# 6_Pulse_Sensor.net
KiCad netlist of a schematic drawn in Altium Designer
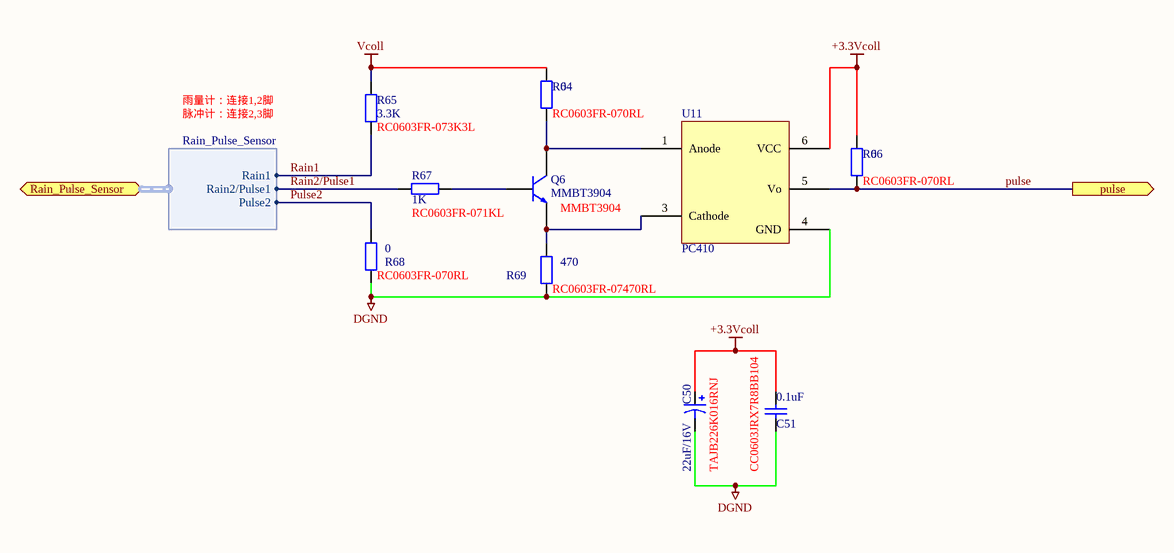
[diagram p0: 6_Pulse_Sensor.SchDoc]

(export (version "E")
  (design (tool "Eeschema 10.0.6"))
  (components
    (comp (ref "C50")
      (value "22uF/16V")
      (footprint "CB3528")
      (description "Polarized Capacitor (Radial)")
      (fields (field (name "PART NO.") "TAJB226K016RNJ"))
      (libsource (lib "Miscellaneous Devices") (part "Cap Pol1"))
    )
    (comp (ref "C51")
      (value "0.1uF")
      (footprint "CC0603")
      (description "Capacitor")
      (fields (field (name "TYPE NO.") "CC0603JRX7R8BB104"))
      (libsource (lib "Miscellaneous Devices") (part "Cap"))
    )
    (comp (ref "Q6")
      (value "MMBT3904")
      (footprint "SOT-23W")
      (fields (field (name "TYPE NO.") "MMBT3904"))
      (libsource (lib "woylib2015") (part "NPN"))
    )
    (comp (ref "R64")
      (value "0")
      (footprint "CC0603")
      (description "Resistor")
      (fields (field (name "TYPE NO.") "RC0603FR-070RL"))
      (libsource (lib "Miscellaneous Devices") (part "Res2"))
    )
    (comp (ref "R65")
      (value "3.3K")
      (footprint "CC0603")
      (description "Resistor")
      (fields (field (name "TYPE NO.") "RC0603FR-073K3L"))
      (libsource (lib "Miscellaneous Devices") (part "Res2"))
    )
    (comp (ref "R66")
      (value "0")
      (footprint "CC0603")
      (description "Resistor")
      (fields (field (name "TYPE NO.") "RC0603FR-070RL"))
      (libsource (lib "Miscellaneous Devices") (part "Res2"))
    )
    (comp (ref "R67")
      (value "1K")
      (footprint "CC0603")
      (description "Resistor")
      (fields (field (name "TYPE NO.") "RC0603FR-071KL"))
      (libsource (lib "") (part "Res2_1"))
    )
    (comp (ref "R68")
      (value "0")
      (footprint "CC0603")
      (description "Resistor")
      (fields (field (name "TYPE NO.") "RC0603FR-070RL"))
      (libsource (lib "Miscellaneous Devices") (part "Res2"))
    )
    (comp (ref "R69")
      (value "470")
      (footprint "CC0603")
      (description "Resistor")
      (fields (field (name "TYPE NO.") "RC0603FR-07470RL"))
      (libsource (lib "Miscellaneous Devices") (part "Res2"))
    )
    (comp (ref "U11") (value "PC410") (footprint "PC410") (libsource (lib "woylib2015") (part "PC410")))
  )
  (nets
    (net (code "2") (name "+3.3Vcoll") (class "Default")
      (node (ref "C50") (pin "1") (pinfunction "1_1") (pintype "passive"))
      (node (ref "C51") (pin "2") (pinfunction "2_2") (pintype "passive"))
      (node (ref "R66") (pin "1") (pinfunction "1_1") (pintype "passive"))
      (node (ref "U11") (pin "6") (pinfunction "VCC_6") (pintype "passive"))
    )
    (net (code "3") (name "/Pulse2") (class "Default")
      (node (ref "R68") (pin "1") (pinfunction "1_1") (pintype "passive"))
    )
    (net (code "4") (name "/Rain1") (class "Default")
      (node (ref "R65") (pin "2") (pinfunction "2_2") (pintype "passive"))
    )
    (net (code "5") (name "/Rain2{slash}Pulse1") (class "Default")
      (node (ref "R67") (pin "1") (pinfunction "1_1") (pintype "passive"))
    )
    (net (code "6") (name "/pulse") (class "Default")
      (node (ref "R66") (pin "2") (pinfunction "2_2") (pintype "passive"))
      (node (ref "U11") (pin "5") (pinfunction "Vo_5") (pintype "passive"))
    )
    (net (code "8") (name "DGND") (class "Default")
      (node (ref "C50") (pin "2") (pinfunction "2_2") (pintype "passive"))
      (node (ref "C51") (pin "1") (pinfunction "1_1") (pintype "passive"))
      (node (ref "R68") (pin "2") (pinfunction "2_2") (pintype "passive"))
      (node (ref "R69") (pin "2") (pinfunction "2_2") (pintype "passive"))
      (node (ref "U11") (pin "4") (pinfunction "GND_4") (pintype "passive"))
    )
    (net (code "9") (name "Net-(Q6-Pad1)") (class "Default")
      (node (ref "Q6") (pin "1") (pinfunction "1_1") (pintype "passive"))
      (node (ref "R67") (pin "2") (pinfunction "2_2") (pintype "passive"))
    )
    (net (code "10") (name "Net-(U11-Anode)") (class "Default")
      (node (ref "Q6") (pin "3") (pinfunction "3_3") (pintype "passive"))
      (node (ref "R64") (pin "2") (pinfunction "2_2") (pintype "passive"))
      (node (ref "U11") (pin "1") (pinfunction "Anode_1") (pintype "passive"))
    )
    (net (code "11") (name "Net-(U11-Cathode)") (class "Default")
      (node (ref "Q6") (pin "2") (pinfunction "2_2") (pintype "passive"))
      (node (ref "R69") (pin "1") (pinfunction "1_1") (pintype "passive"))
      (node (ref "U11") (pin "3") (pinfunction "Cathode_3") (pintype "passive"))
    )
    (net (code "12") (name "Vcoll") (class "Default")
      (node (ref "R64") (pin "1") (pinfunction "1_1") (pintype "passive"))
      (node (ref "R65") (pin "1") (pinfunction "1_1") (pintype "passive"))
    )
  )
)
